# MEAS-ADXL354.net
KiCad netlist of a schematic drawn in EAGLE
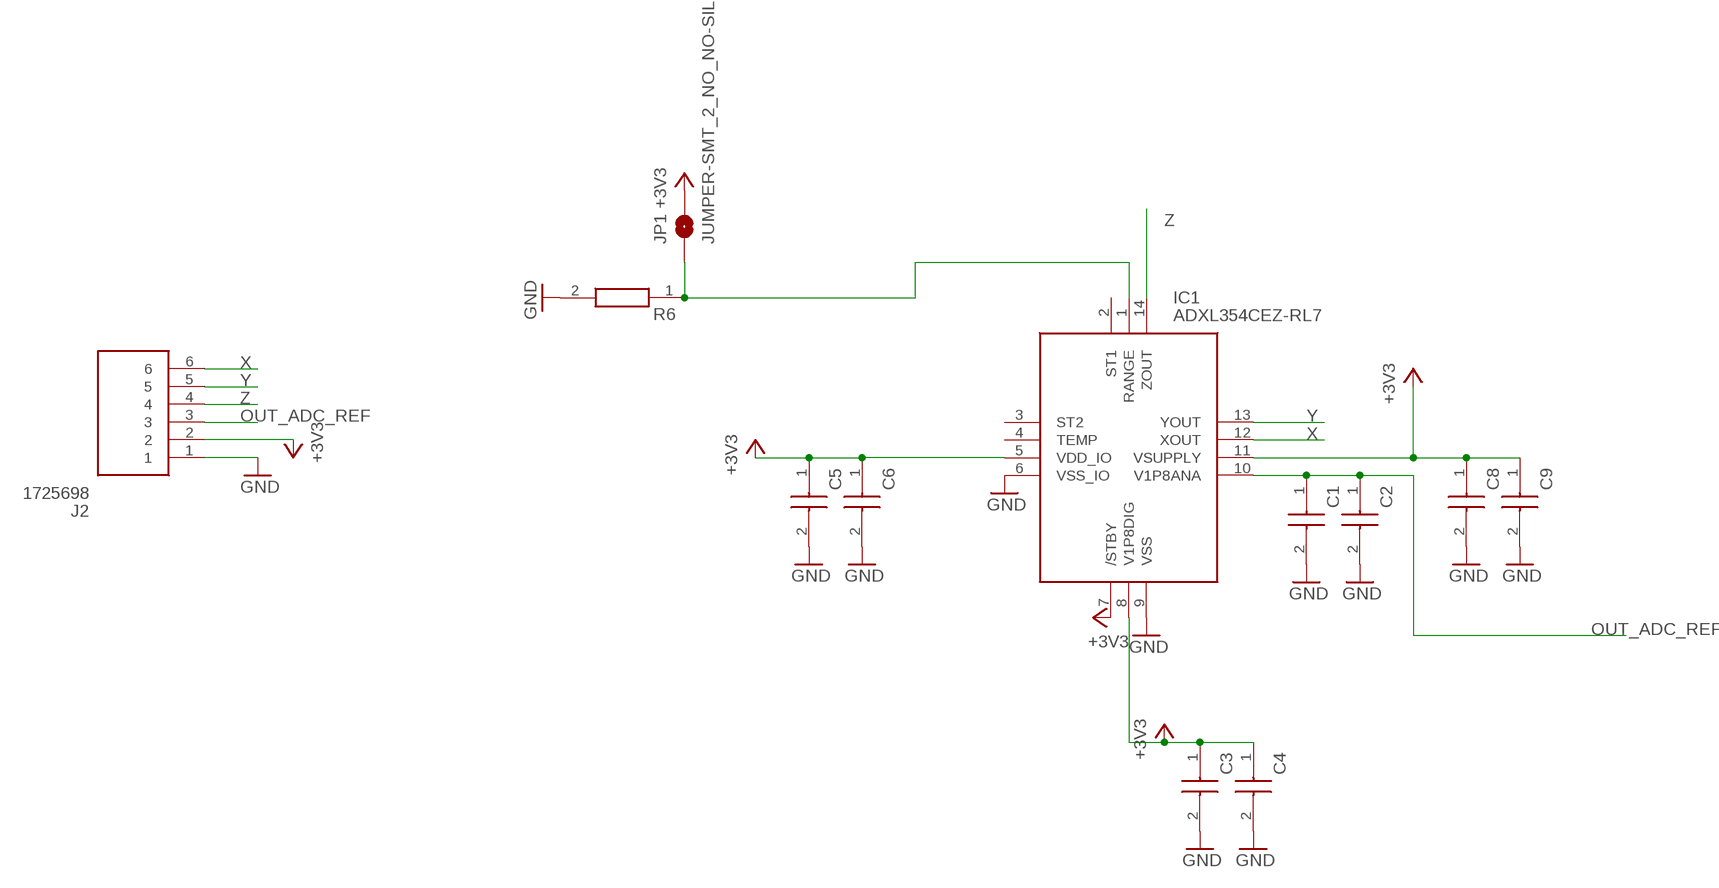
[diagram p0: schematic, sheet 1]

(export (version "E")
  (design (tool "Eeschema 10.0.6"))
  (components
    (comp (ref "C1")
      (value "1.0uF")
      (footprint "eagle-import:CAPC1005X55N")
      (fields
        (field (name "MANUFACTURER_PART_NUMBER") "LMK105BJ225KV-F")
        (field (name "MOUSER_PART_NUMBER") "963-LMK105BJ225KV-F")
      )
      (libsource (lib "eagle-import") (part "LMK105BJ225KV-F"))
    )
    (comp (ref "C2")
      (value "0.1uF")
      (footprint "eagle-import:CAPC1005X55N")
      (fields
        (field (name "MANUFACTURER_PART_NUMBER") "885012105010")
        (field (name "MOUSER_PART_NUMBER") "710-885012105010")
      )
      (libsource (lib "eagle-import") (part "885012105010"))
    )
    (comp (ref "C3")
      (value "1.0uF")
      (footprint "eagle-import:CAPC1005X55N")
      (fields
        (field (name "MANUFACTURER_PART_NUMBER") "LMK105BJ225KV-F")
        (field (name "MOUSER_PART_NUMBER") "963-LMK105BJ225KV-F")
      )
      (libsource (lib "eagle-import") (part "LMK105BJ225KV-F"))
    )
    (comp (ref "C4")
      (value "0.1uF")
      (footprint "eagle-import:CAPC1005X55N")
      (fields
        (field (name "MANUFACTURER_PART_NUMBER") "885012105010")
        (field (name "MOUSER_PART_NUMBER") "710-885012105010")
      )
      (libsource (lib "eagle-import") (part "885012105010"))
    )
    (comp (ref "C5")
      (value "1.0uF")
      (footprint "eagle-import:CAPC1005X55N")
      (fields
        (field (name "MANUFACTURER_PART_NUMBER") "LMK105BJ225KV-F")
        (field (name "MOUSER_PART_NUMBER") "963-LMK105BJ225KV-F")
      )
      (libsource (lib "eagle-import") (part "LMK105BJ225KV-F"))
    )
    (comp (ref "C6")
      (value "0.1uF")
      (footprint "eagle-import:CAPC1005X55N")
      (fields
        (field (name "MANUFACTURER_PART_NUMBER") "885012105010")
        (field (name "MOUSER_PART_NUMBER") "710-885012105010")
      )
      (libsource (lib "eagle-import") (part "885012105010"))
    )
    (comp (ref "C8")
      (value "1.0uF")
      (footprint "eagle-import:CAPC1005X55N")
      (fields
        (field (name "MANUFACTURER_PART_NUMBER") "LMK105BJ225KV-F")
        (field (name "MOUSER_PART_NUMBER") "963-LMK105BJ225KV-F")
      )
      (libsource (lib "eagle-import") (part "LMK105BJ225KV-F"))
    )
    (comp (ref "C9")
      (value "0.1uF")
      (footprint "eagle-import:CAPC1005X55N")
      (fields
        (field (name "MANUFACTURER_PART_NUMBER") "885012105010")
        (field (name "MOUSER_PART_NUMBER") "710-885012105010")
      )
      (libsource (lib "eagle-import") (part "885012105010"))
    )
    (comp (ref "IC1")
      (value "ADXL354CEZ-RL7")
      (footprint "eagle-import:PLCC127P602X560X205-14N")
      (libsource (lib "eagle-import") (part "ADXL354CEZ-RL7"))
    )
    (comp (ref "J2")
      (value "1725698")
      (footprint "eagle-import:1725698")
      (fields (field (name "MOUSER_PART_NUMBER") "651-1725698"))
      (libsource (lib "eagle-import") (part "1725698"))
    )
    (comp (ref "JP1")
      (value "JUMPER-SMT_2_NO_NO-SILK")
      (footprint "eagle-import:SMT-JUMPER_2_NO_NO-SILK")
      (libsource (lib "eagle-import") (part "JUMPER-SMT_2_NO_NO-SILK"))
    )
    (comp (ref "R6")
      (value "SFR03EZPF6801")
      (footprint "eagle-import:RESC1608X55N")
      (libsource (lib "eagle-import") (part "SFR03EZPF6801"))
    )
  )
  (nets
    (net (code "1") (name "+3V3") (class "Default")
      (node (ref "C3") (pin "1") (pinfunction "1_1") (pintype "bidirectional"))
      (node (ref "C4") (pin "1") (pinfunction "1_1") (pintype "bidirectional"))
      (node (ref "C5") (pin "1") (pinfunction "1_1") (pintype "bidirectional"))
      (node (ref "C6") (pin "1") (pinfunction "1_1") (pintype "bidirectional"))
      (node (ref "C8") (pin "1") (pinfunction "1_1") (pintype "bidirectional"))
      (node (ref "C9") (pin "1") (pinfunction "1_1") (pintype "bidirectional"))
      (node (ref "IC1") (pin "11") (pinfunction "VSUPPLY_11") (pintype "bidirectional"))
      (node (ref "IC1") (pin "5") (pinfunction "VDD_IO_5") (pintype "bidirectional"))
      (node (ref "IC1") (pin "7") (pinfunction "/STBY_7") (pintype "bidirectional"))
      (node (ref "IC1") (pin "8") (pinfunction "V1P8DIG_8") (pintype "bidirectional"))
      (node (ref "J2") (pin "2") (pinfunction "2_2") (pintype "bidirectional"))
      (node (ref "JP1") (pin "2") (pinfunction "2_2") (pintype "passive"))
    )
    (net (code "2") (name "/OUT_ADC_REF") (class "Default")
      (node (ref "C1") (pin "1") (pinfunction "1_1") (pintype "bidirectional"))
      (node (ref "C2") (pin "1") (pinfunction "1_1") (pintype "bidirectional"))
      (node (ref "IC1") (pin "10") (pinfunction "V1P8ANA_10") (pintype "bidirectional"))
      (node (ref "J2") (pin "3") (pinfunction "3_3") (pintype "bidirectional"))
    )
    (net (code "3") (name "/X") (class "Default")
      (node (ref "IC1") (pin "12") (pinfunction "XOUT_12") (pintype "bidirectional"))
      (node (ref "J2") (pin "6") (pinfunction "6_6") (pintype "bidirectional"))
    )
    (net (code "4") (name "/Y") (class "Default")
      (node (ref "IC1") (pin "13") (pinfunction "YOUT_13") (pintype "bidirectional"))
      (node (ref "J2") (pin "5") (pinfunction "5_5") (pintype "bidirectional"))
    )
    (net (code "5") (name "/Z") (class "Default")
      (node (ref "IC1") (pin "14") (pinfunction "ZOUT_14") (pintype "bidirectional"))
      (node (ref "J2") (pin "4") (pinfunction "4_4") (pintype "bidirectional"))
    )
    (net (code "6") (name "GND") (class "Default")
      (node (ref "C1") (pin "2") (pinfunction "2_2") (pintype "bidirectional"))
      (node (ref "C2") (pin "2") (pinfunction "2_2") (pintype "bidirectional"))
      (node (ref "C3") (pin "2") (pinfunction "2_2") (pintype "bidirectional"))
      (node (ref "C4") (pin "2") (pinfunction "2_2") (pintype "bidirectional"))
      (node (ref "C5") (pin "2") (pinfunction "2_2") (pintype "bidirectional"))
      (node (ref "C6") (pin "2") (pinfunction "2_2") (pintype "bidirectional"))
      (node (ref "C8") (pin "2") (pinfunction "2_2") (pintype "bidirectional"))
      (node (ref "C9") (pin "2") (pinfunction "2_2") (pintype "bidirectional"))
      (node (ref "IC1") (pin "6") (pinfunction "VSS_IO_6") (pintype "bidirectional"))
      (node (ref "IC1") (pin "9") (pinfunction "VSS_9") (pintype "bidirectional"))
      (node (ref "J2") (pin "1") (pinfunction "1_1") (pintype "bidirectional"))
      (node (ref "R6") (pin "2") (pinfunction "2_2") (pintype "bidirectional"))
    )
    (net (code "7") (name "Net-(IC1-RANGE)") (class "Default")
      (node (ref "IC1") (pin "1") (pinfunction "RANGE_1") (pintype "bidirectional"))
      (node (ref "JP1") (pin "1") (pinfunction "1_1") (pintype "passive"))
      (node (ref "R6") (pin "1") (pinfunction "1_1") (pintype "bidirectional"))
    )
    (net (code "8") (name "unconnected-(IC1-ST1-Pad2)") (class "Default")
      (node (ref "IC1") (pin "2") (pinfunction "ST1_2") (pintype "bidirectional"))
    )
    (net (code "9") (name "unconnected-(IC1-ST2-Pad3)") (class "Default")
      (node (ref "IC1") (pin "3") (pinfunction "ST2_3") (pintype "bidirectional"))
    )
    (net (code "10") (name "unconnected-(IC1-TEMP-Pad4)") (class "Default")
      (node (ref "IC1") (pin "4") (pinfunction "TEMP_4") (pintype "bidirectional"))
    )
  )
)
